# RevisionA.net
KiCad netlist of a schematic drawn in EAGLE
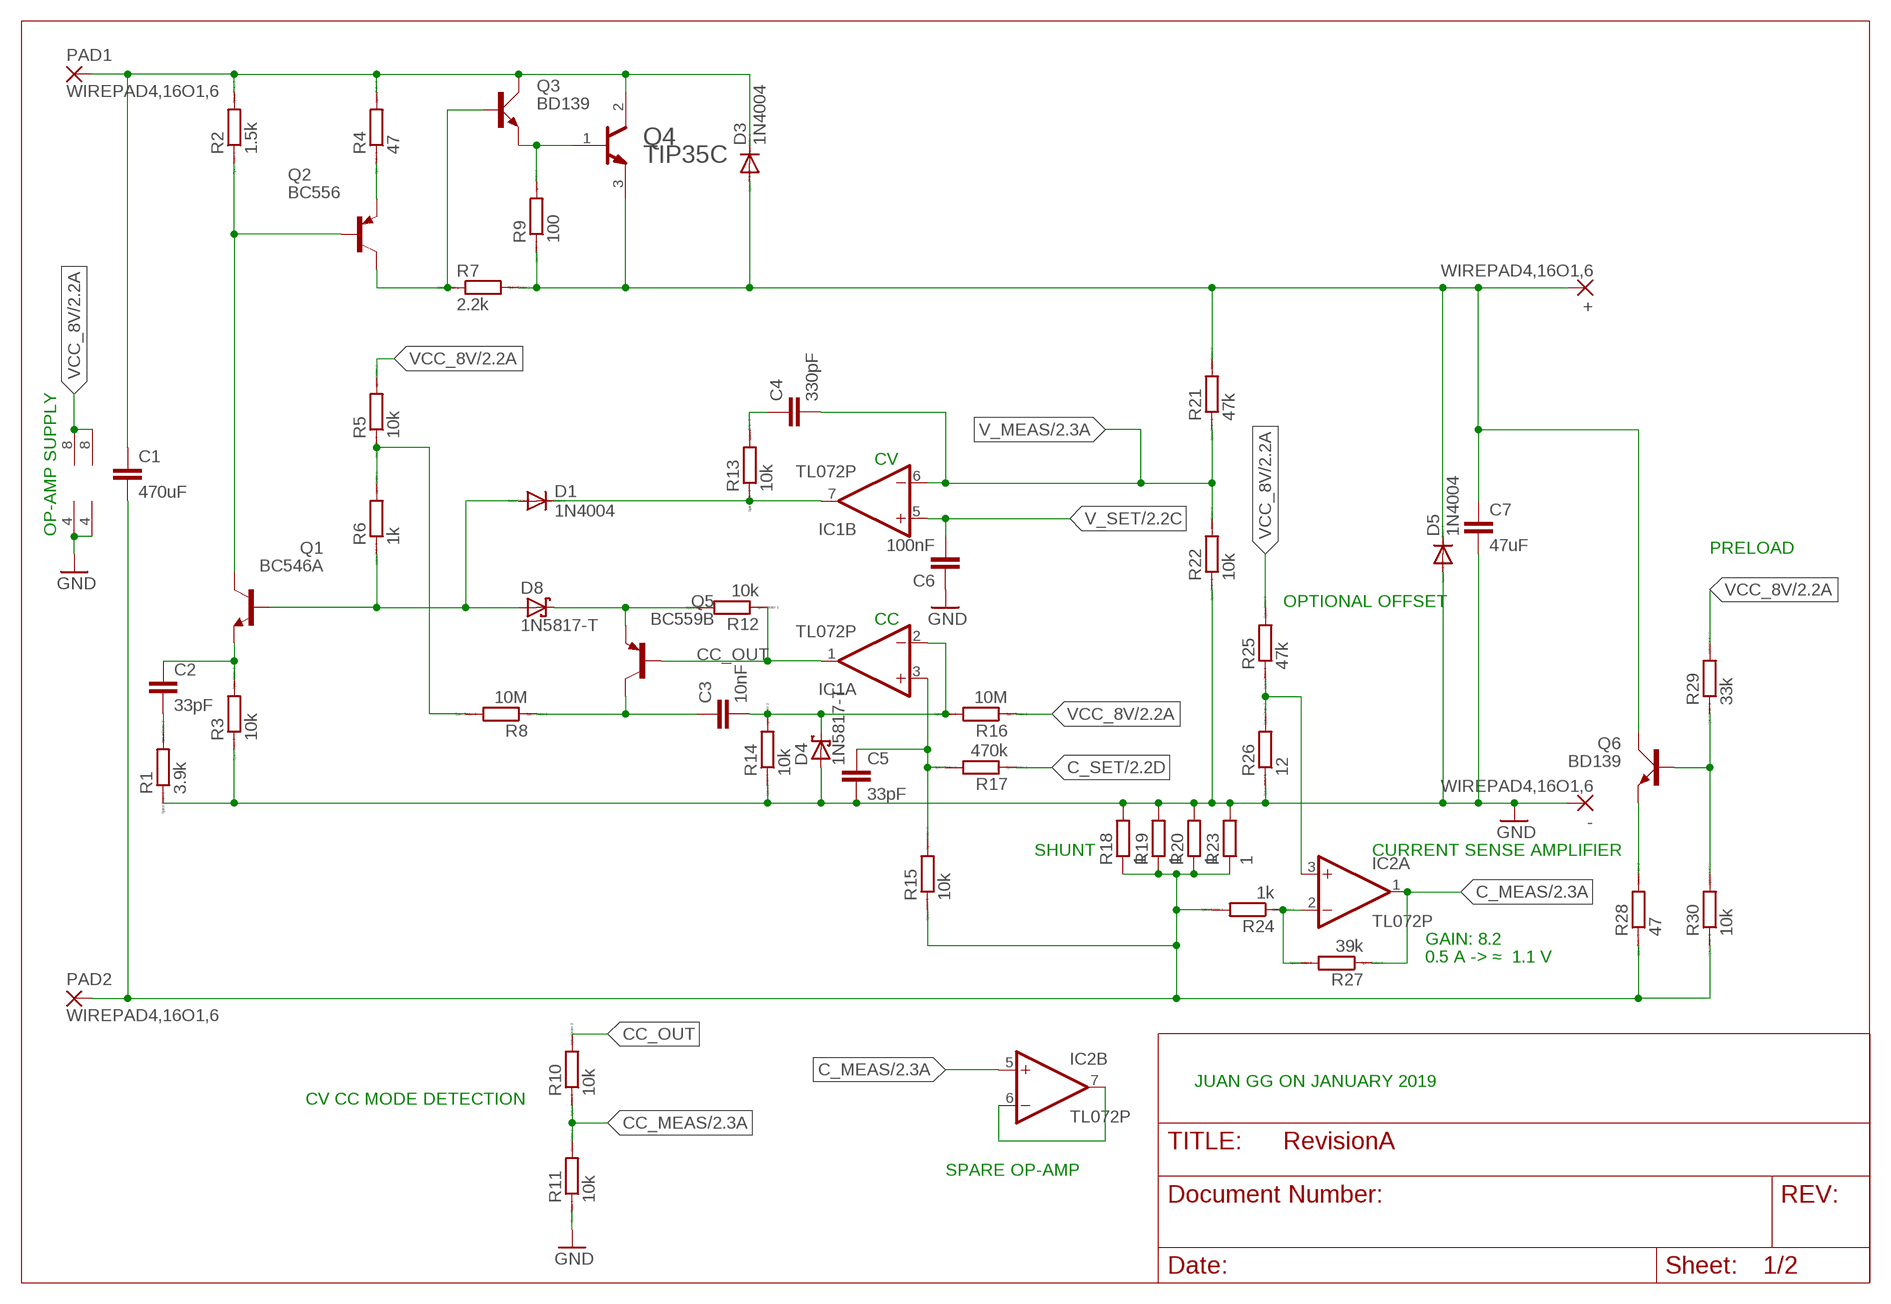
[diagram p0: schematic, sheet 1]
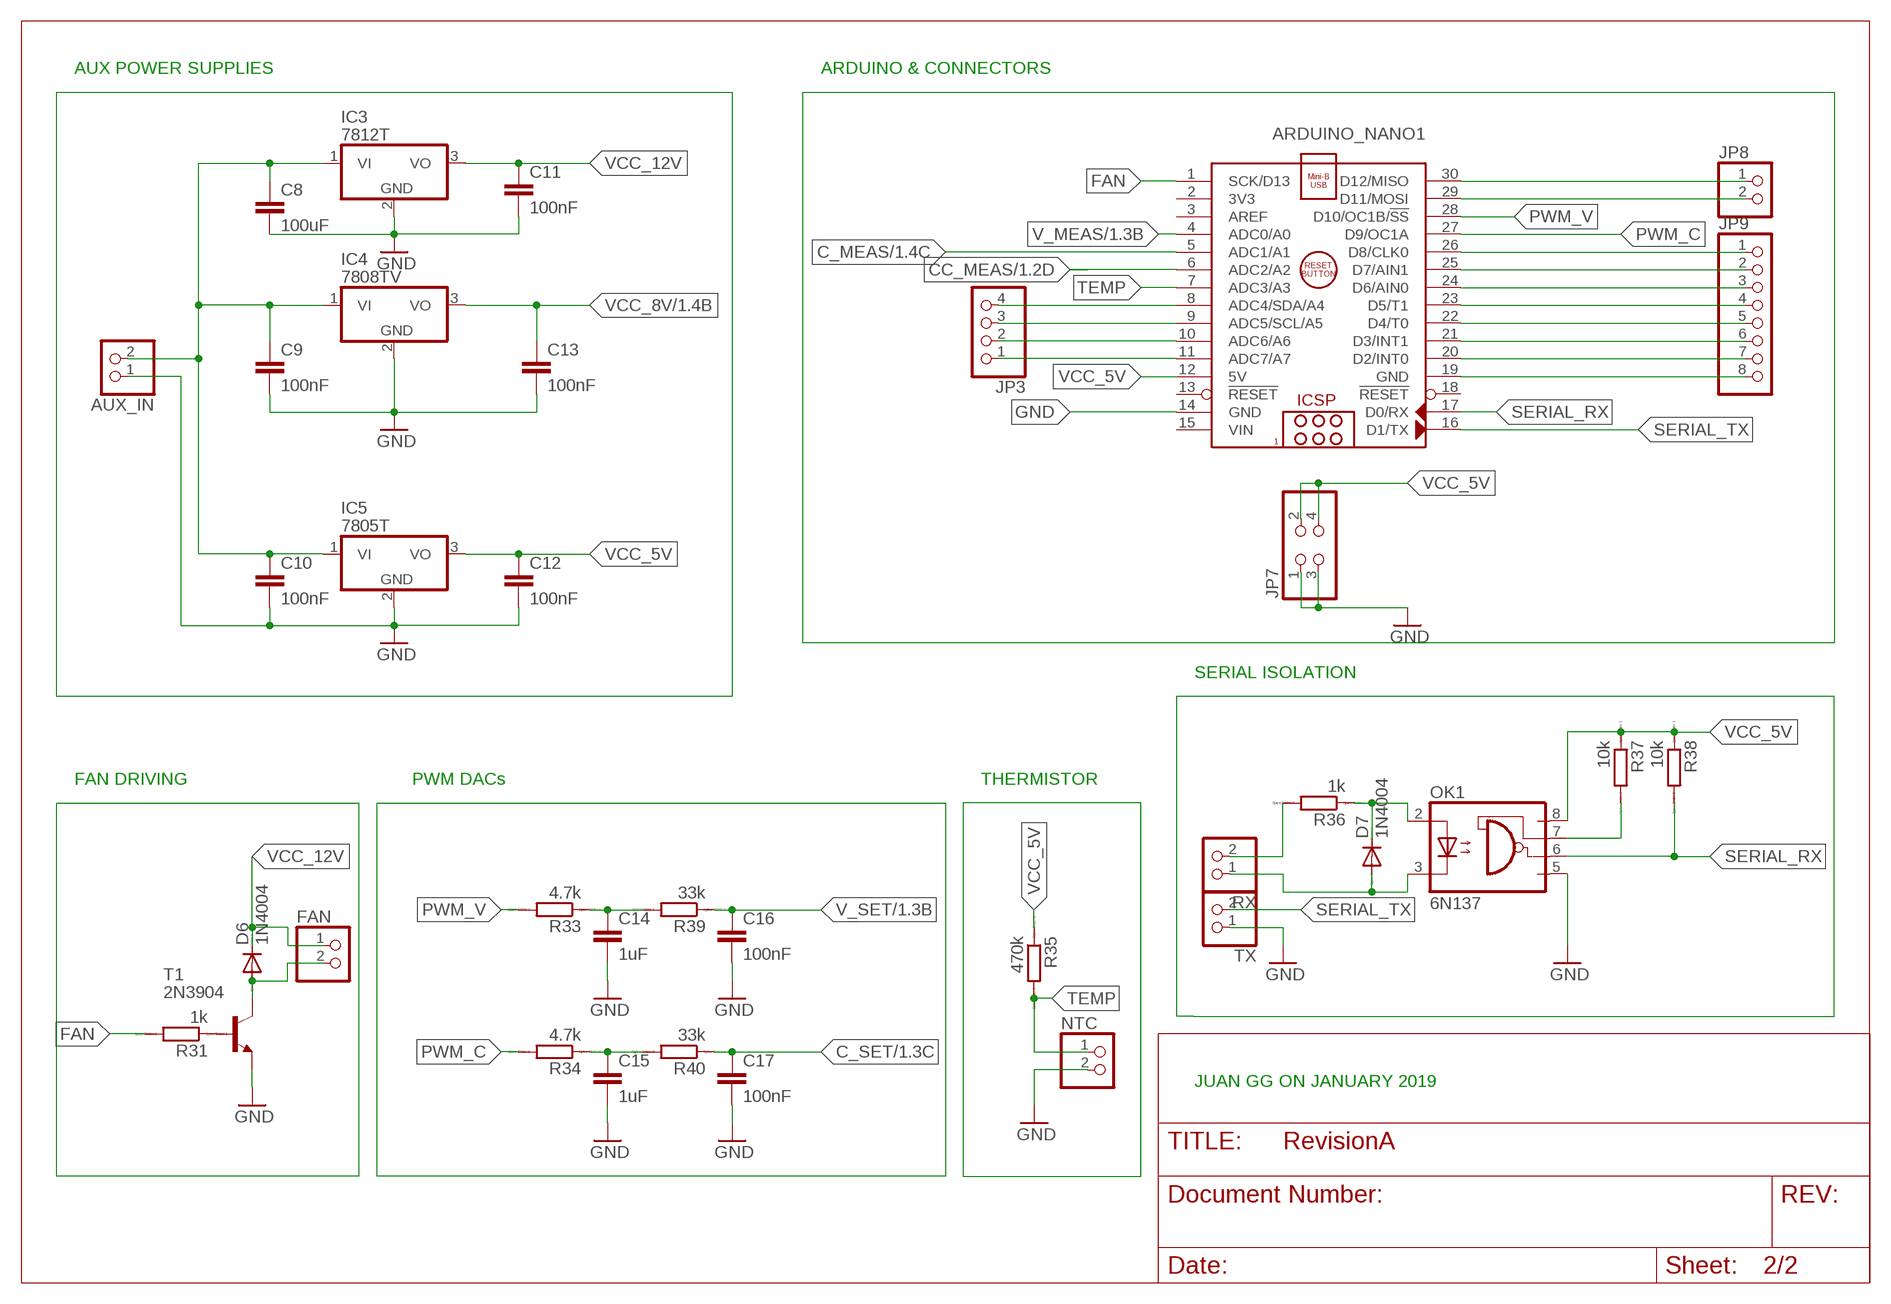
[diagram p1: schematic, sheet 2]

(export (version "E")
  (design (tool "Eeschema 10.0.6"))
  (components
    (comp (ref "+")
      (value "WIREPAD4,16O1,6")
      (footprint "eagle-import:4,16O1,6")
      (libsource (lib "eagle-import") (part "WIREPAD4,16O1,6"))
    )
    (comp (ref "-")
      (value "WIREPAD4,16O1,6")
      (footprint "eagle-import:4,16O1,6")
      (libsource (lib "eagle-import") (part "WIREPAD4,16O1,6"))
    )
    (comp (ref "C1")
      (value "470uF")
      (footprint "eagle-import:C5B7.2")
      (libsource (lib "eagle-import") (part "C5/7.2"))
    )
    (comp (ref "C2")
      (value "33pF")
      (footprint "eagle-import:C2.5-2")
      (libsource (lib "eagle-import") (part "C2.5/2"))
    )
    (comp (ref "C3")
      (value "10nF")
      (footprint "eagle-import:C2.5-2")
      (libsource (lib "eagle-import") (part "C2.5/2"))
    )
    (comp (ref "C4")
      (value "330pF")
      (footprint "eagle-import:C2.5-2")
      (libsource (lib "eagle-import") (part "C2.5/2"))
    )
    (comp (ref "C5")
      (value "33pF")
      (footprint "eagle-import:C2.5-2")
      (libsource (lib "eagle-import") (part "C2.5/2"))
    )
    (comp (ref "C6")
      (value "100nF")
      (footprint "eagle-import:C2.5-2")
      (libsource (lib "eagle-import") (part "C2.5/2"))
    )
    (comp (ref "C7")
      (value "47uF")
      (footprint "eagle-import:C5B7.2")
      (libsource (lib "eagle-import") (part "C5/7.2"))
    )
    (comp (ref "D1")
      (value "1N4004")
      (footprint "eagle-import:DO41-10")
      (libsource (lib "eagle-import") (part "1N4004"))
    )
    (comp (ref "D3")
      (value "1N4004")
      (footprint "eagle-import:DO41-10")
      (libsource (lib "eagle-import") (part "1N4004"))
    )
    (comp (ref "D4")
      (value "1N5817-T")
      (footprint "eagle-import:DO41-7.6")
      (libsource (lib "eagle-import") (part "1N5817-T"))
    )
    (comp (ref "D5")
      (value "1N4004")
      (footprint "eagle-import:DO41-10")
      (libsource (lib "eagle-import") (part "1N4004"))
    )
    (comp (ref "D8")
      (value "1N5817-T")
      (footprint "eagle-import:DO41-7.6")
      (libsource (lib "eagle-import") (part "1N5817-T"))
    )
    (comp (ref "IC1")
      (value "TL072P")
      (footprint "eagle-import:DIL08")
      (libsource (lib "eagle-import") (part "TL072P"))
    )
    (comp (ref "IC2")
      (value "TL072P")
      (footprint "eagle-import:DIL08")
      (libsource (lib "eagle-import") (part "TL072P"))
    )
    (comp (ref "PAD1")
      (value "WIREPAD4,16O1,6")
      (footprint "eagle-import:4,16O1,6")
      (libsource (lib "eagle-import") (part "WIREPAD4,16O1,6"))
    )
    (comp (ref "PAD2")
      (value "WIREPAD4,16O1,6")
      (footprint "eagle-import:4,16O1,6")
      (libsource (lib "eagle-import") (part "WIREPAD4,16O1,6"))
    )
    (comp (ref "Q1")
      (value "BC546A")
      (footprint "eagle-import:TO92-EBC")
      (libsource (lib "eagle-import") (part "BC546A"))
    )
    (comp (ref "Q2")
      (value "BC556")
      (footprint "eagle-import:TO92-EBC")
      (libsource (lib "eagle-import") (part "BC556"))
    )
    (comp (ref "Q3")
      (value "BD139")
      (footprint "eagle-import:TO126AV")
      (libsource (lib "eagle-import") (part "BD139"))
    )
    (comp (ref "Q4")
      (value "STMICROELECTRONICS_TIP35CSTMICROELECTRONICS_TIP35C_0_0")
      (footprint "eagle-import:STMICROELECTRONICS_TIP35C_0")
      (fields
        (field (name "DIGIKEY_PART_NUMBER") "497-2609-5-ND")
        (field (name "MF") "STMicroelectronics")
        (field (name "MOUSER_PART_NUMBER") "511-TIP35C")
      )
      (libsource (lib "eagle-import") (part "STMICROELECTRONICS_TIP35CSTMICROELECTRONICS_TIP35C_0_0"))
    )
    (comp (ref "Q5")
      (value "BC559B")
      (footprint "eagle-import:TO92-EBC")
      (libsource (lib "eagle-import") (part "BC559B"))
    )
    (comp (ref "Q6")
      (value "BD139")
      (footprint "eagle-import:TO126AV")
      (libsource (lib "eagle-import") (part "BD139"))
    )
    (comp (ref "R1")
      (value "3.9k")
      (footprint "eagle-import:0207_10")
      (libsource (lib "eagle-import") (part "R0207/10"))
    )
    (comp (ref "R2")
      (value "1.5k")
      (footprint "eagle-import:0207_10")
      (libsource (lib "eagle-import") (part "R0207/10"))
    )
    (comp (ref "R3")
      (value "10k")
      (footprint "eagle-import:0207_10")
      (libsource (lib "eagle-import") (part "R0207/10"))
    )
    (comp (ref "R4")
      (value "47")
      (footprint "eagle-import:0207_10")
      (libsource (lib "eagle-import") (part "R0207/10"))
    )
    (comp (ref "R5")
      (value "10k")
      (footprint "eagle-import:0207_10")
      (libsource (lib "eagle-import") (part "R0207/10"))
    )
    (comp (ref "R6")
      (value "1k")
      (footprint "eagle-import:0207_10")
      (libsource (lib "eagle-import") (part "R0207/10"))
    )
    (comp (ref "R7")
      (value "2.2k")
      (footprint "eagle-import:0207_10")
      (libsource (lib "eagle-import") (part "R0207/10"))
    )
    (comp (ref "R8")
      (value "10M")
      (footprint "eagle-import:0207_10")
      (libsource (lib "eagle-import") (part "R0207/10"))
    )
    (comp (ref "R9")
      (value "100")
      (footprint "eagle-import:0207_10")
      (libsource (lib "eagle-import") (part "R0207/10"))
    )
    (comp (ref "R10")
      (value "10k")
      (footprint "eagle-import:0207_10")
      (libsource (lib "eagle-import") (part "R0207/10"))
    )
    (comp (ref "R11")
      (value "10k")
      (footprint "eagle-import:0207_10")
      (libsource (lib "eagle-import") (part "R0207/10"))
    )
    (comp (ref "R12")
      (value "10k")
      (footprint "eagle-import:0207_10")
      (libsource (lib "eagle-import") (part "R0207/10"))
    )
    (comp (ref "R13")
      (value "10k")
      (footprint "eagle-import:0207_10")
      (libsource (lib "eagle-import") (part "R0207/10"))
    )
    (comp (ref "R14")
      (value "10k")
      (footprint "eagle-import:0207_10")
      (libsource (lib "eagle-import") (part "R0207/10"))
    )
    (comp (ref "R15")
      (value "10k")
      (footprint "eagle-import:0207_10")
      (libsource (lib "eagle-import") (part "R0207/10"))
    )
    (comp (ref "R16")
      (value "10M")
      (footprint "eagle-import:0207_10")
      (libsource (lib "eagle-import") (part "R0207/10"))
    )
    (comp (ref "R17")
      (value "470k")
      (footprint "eagle-import:0207_10")
      (libsource (lib "eagle-import") (part "R0207/10"))
    )
    (comp (ref "R18")
      (value "1")
      (footprint "eagle-import:0617V")
      (libsource (lib "eagle-import") (part "R-EU_0617/5V"))
    )
    (comp (ref "R19")
      (value "1")
      (footprint "eagle-import:0617V")
      (libsource (lib "eagle-import") (part "R-EU_0617/5V"))
    )
    (comp (ref "R20")
      (value "1")
      (footprint "eagle-import:0617V")
      (libsource (lib "eagle-import") (part "R-EU_0617/5V"))
    )
    (comp (ref "R21")
      (value "47k")
      (footprint "eagle-import:0207_10")
      (libsource (lib "eagle-import") (part "R0207/10"))
    )
    (comp (ref "R22")
      (value "10k")
      (footprint "eagle-import:0207_10")
      (libsource (lib "eagle-import") (part "R0207/10"))
    )
    (comp (ref "R23")
      (value "1")
      (footprint "eagle-import:0617V")
      (libsource (lib "eagle-import") (part "R-EU_0617/5V"))
    )
    (comp (ref "R24")
      (value "1k")
      (footprint "eagle-import:0207_10")
      (libsource (lib "eagle-import") (part "R0207/10"))
    )
    (comp (ref "R25")
      (value "47k")
      (footprint "eagle-import:0207_10")
      (libsource (lib "eagle-import") (part "R0207/10"))
    )
    (comp (ref "R26")
      (value "12")
      (footprint "eagle-import:0207_10")
      (libsource (lib "eagle-import") (part "R0207/10"))
    )
    (comp (ref "R27")
      (value "39k")
      (footprint "eagle-import:0207_10")
      (libsource (lib "eagle-import") (part "R0207/10"))
    )
    (comp (ref "R28")
      (value "47")
      (footprint "eagle-import:0207_10")
      (libsource (lib "eagle-import") (part "R0207/10"))
    )
    (comp (ref "R29")
      (value "33k")
      (footprint "eagle-import:0207_10")
      (libsource (lib "eagle-import") (part "R0207/10"))
    )
    (comp (ref "R30")
      (value "10k")
      (footprint "eagle-import:0207_10")
      (libsource (lib "eagle-import") (part "R0207/10"))
    )
    (comp (ref "ARDUINO_NANO1")
      (value "ARDUINO_NANO")
      (footprint "eagle-import:ARDUINO_NANO")
      (libsource (lib "eagle-import") (part "ARDUINO_NANO"))
    )
    (comp (ref "AUX_IN")
      (value "PINHD-1X2")
      (footprint "eagle-import:1X02")
      (libsource (lib "eagle-import") (part "PINHD-1X2"))
    )
    (comp (ref "C8")
      (value "100uF")
      (footprint "eagle-import:C2.5-4")
      (libsource (lib "eagle-import") (part "C2.5/4"))
    )
    (comp (ref "C9")
      (value "100nF")
      (footprint "eagle-import:C2.5-2")
      (libsource (lib "eagle-import") (part "C2.5/2"))
    )
    (comp (ref "C10")
      (value "100nF")
      (footprint "eagle-import:C2.5-2")
      (libsource (lib "eagle-import") (part "C2.5/2"))
    )
    (comp (ref "C11")
      (value "100nF")
      (footprint "eagle-import:C2.5-2")
      (libsource (lib "eagle-import") (part "C2.5/2"))
    )
    (comp (ref "C12")
      (value "100nF")
      (footprint "eagle-import:C2.5-2")
      (libsource (lib "eagle-import") (part "C2.5/2"))
    )
    (comp (ref "C13")
      (value "100nF")
      (footprint "eagle-import:C2.5-2")
      (libsource (lib "eagle-import") (part "C2.5/2"))
    )
    (comp (ref "C14")
      (value "1uF")
      (footprint "eagle-import:C2.5-4")
      (libsource (lib "eagle-import") (part "C2.5/4"))
    )
    (comp (ref "C15")
      (value "1uF")
      (footprint "eagle-import:C2.5-4")
      (libsource (lib "eagle-import") (part "C2.5/4"))
    )
    (comp (ref "C16")
      (value "100nF")
      (footprint "eagle-import:C2.5-4")
      (libsource (lib "eagle-import") (part "C2.5/4"))
    )
    (comp (ref "C17")
      (value "100nF")
      (footprint "eagle-import:C2.5-4")
      (libsource (lib "eagle-import") (part "C2.5/4"))
    )
    (comp (ref "D6")
      (value "1N4004")
      (footprint "eagle-import:DO41-10")
      (libsource (lib "eagle-import") (part "1N4004"))
    )
    (comp (ref "D7")
      (value "1N4004")
      (footprint "eagle-import:DO41-10")
      (libsource (lib "eagle-import") (part "1N4004"))
    )
    (comp (ref "FAN")
      (value "PINHD-1X2")
      (footprint "eagle-import:1X02")
      (libsource (lib "eagle-import") (part "PINHD-1X2"))
    )
    (comp (ref "IC3")
      (value "7812T")
      (footprint "eagle-import:TO220H")
      (libsource (lib "eagle-import") (part "78T12"))
    )
    (comp (ref "IC4")
      (value "7808TV")
      (footprint "eagle-import:TO220H")
      (libsource (lib "eagle-import") (part "78T12"))
    )
    (comp (ref "IC5")
      (value "7805T")
      (footprint "eagle-import:TO220H")
      (libsource (lib "eagle-import") (part "78T05"))
    )
    (comp (ref "JP3")
      (value "PINHD-1X4")
      (footprint "eagle-import:1X04")
      (libsource (lib "eagle-import") (part "PINHD-1X4"))
    )
    (comp (ref "JP7")
      (value "PINHD-2X2")
      (footprint "eagle-import:2X02")
      (libsource (lib "eagle-import") (part "PINHD-2X2"))
    )
    (comp (ref "JP8")
      (value "PINHD-1X2")
      (footprint "eagle-import:1X02")
      (libsource (lib "eagle-import") (part "PINHD-1X2"))
    )
    (comp (ref "JP9")
      (value "PINHD-1X8")
      (footprint "eagle-import:1X08")
      (libsource (lib "eagle-import") (part "PINHD-1X8"))
    )
    (comp (ref "NTC")
      (value "PINHD-1X2")
      (footprint "eagle-import:1X02")
      (libsource (lib "eagle-import") (part "PINHD-1X2"))
    )
    (comp (ref "OK1")
      (value "6N137")
      (footprint "eagle-import:DIL08")
      (libsource (lib "eagle-import") (part "6N137"))
    )
    (comp (ref "R31")
      (value "1k")
      (footprint "eagle-import:0207_10")
      (libsource (lib "eagle-import") (part "R0207/10"))
    )
    (comp (ref "R33")
      (value "4.7k")
      (footprint "eagle-import:0207_10")
      (libsource (lib "eagle-import") (part "R0207/10"))
    )
    (comp (ref "R34")
      (value "4.7k")
      (footprint "eagle-import:0207_10")
      (libsource (lib "eagle-import") (part "R0207/10"))
    )
    (comp (ref "R35")
      (value "470k")
      (footprint "eagle-import:0207_10")
      (libsource (lib "eagle-import") (part "R0207/10"))
    )
    (comp (ref "R36")
      (value "1k")
      (footprint "eagle-import:0207_10")
      (libsource (lib "eagle-import") (part "R0207/10"))
    )
    (comp (ref "R37")
      (value "10k")
      (footprint "eagle-import:0207_10")
      (libsource (lib "eagle-import") (part "R0207/10"))
    )
    (comp (ref "R38")
      (value "10k")
      (footprint "eagle-import:0207_10")
      (libsource (lib "eagle-import") (part "R0207/10"))
    )
    (comp (ref "R39")
      (value "33k")
      (footprint "eagle-import:0207_10")
      (libsource (lib "eagle-import") (part "R0207/10"))
    )
    (comp (ref "R40")
      (value "33k")
      (footprint "eagle-import:0207_10")
      (libsource (lib "eagle-import") (part "R0207/10"))
    )
    (comp (ref "RX")
      (value "PINHD-1X2")
      (footprint "eagle-import:1X02")
      (libsource (lib "eagle-import") (part "PINHD-1X2"))
    )
    (comp (ref "T1")
      (value "2N3904")
      (footprint "eagle-import:TO92")
      (libsource (lib "eagle-import") (part "2N3904"))
    )
    (comp (ref "TX")
      (value "PINHD-1X2")
      (footprint "eagle-import:1X02")
      (libsource (lib "eagle-import") (part "PINHD-1X2"))
    )
  )
  (nets
    (net (code "1") (name "CC_MEAS") (class "Default")
      (node (ref "ARDUINO_NANO1") (pin "6") (pinfunction "ADC2/A2_6") (pintype "bidirectional"))
      (node (ref "R10") (pin "1") (pinfunction "1_1") (pintype "passive"))
      (node (ref "R11") (pin "2") (pinfunction "2_2") (pintype "passive"))
    )
    (net (code "2") (name "CC_OUT") (class "Default")
      (node (ref "IC1") (pin "1") (pinfunction "OUT_1") (pintype "output"))
      (node (ref "Q5") (pin "B") (pinfunction "B_B") (pintype "passive"))
      (node (ref "R10") (pin "2") (pinfunction "2_2") (pintype "passive"))
      (node (ref "R12") (pin "1") (pinfunction "1_1") (pintype "passive"))
    )
    (net (code "3") (name "C_MEAS") (class "Default")
      (node (ref "ARDUINO_NANO1") (pin "5") (pinfunction "ADC1/A1_5") (pintype "bidirectional"))
      (node (ref "IC2") (pin "1") (pinfunction "OUT_1") (pintype "output"))
      (node (ref "IC2") (pin "5") (pinfunction "+IN_5") (pintype "input"))
      (node (ref "R27") (pin "1") (pinfunction "1_1") (pintype "passive"))
    )
    (net (code "4") (name "C_SET") (class "Default")
      (node (ref "C17") (pin "1") (pinfunction "1_1") (pintype "passive"))
      (node (ref "R17") (pin "1") (pinfunction "1_1") (pintype "passive"))
      (node (ref "R40") (pin "1") (pinfunction "1_1") (pintype "passive"))
    )
    (net (code "5") (name "FAN") (class "Default")
      (node (ref "ARDUINO_NANO1") (pin "1") (pinfunction "SCK/D13_1") (pintype "bidirectional"))
      (node (ref "R31") (pin "2") (pinfunction "2_2") (pintype "passive"))
    )
    (net (code "6") (name "GND") (class "Default")
      (node (ref "-") (pin "1") (pinfunction "P_1") (pintype "passive"))
      (node (ref "ARDUINO_NANO1") (pin "14") (pinfunction "GND_14") (pintype "power_in"))
      (node (ref "ARDUINO_NANO1") (pin "19") (pinfunction "GND_19") (pintype "power_in"))
      (node (ref "AUX_IN") (pin "1") (pinfunction "1_1") (pintype "passive"))
      (node (ref "C10") (pin "2") (pinfunction "2_2") (pintype "passive"))
      (node (ref "C11") (pin "2") (pinfunction "2_2") (pintype "passive"))
      (node (ref "C12") (pin "2") (pinfunction "2_2") (pintype "passive"))
      (node (ref "C13") (pin "2") (pinfunction "2_2") (pintype "passive"))
      (node (ref "C14") (pin "2") (pinfunction "2_2") (pintype "passive"))
      (node (ref "C15") (pin "2") (pinfunction "2_2") (pintype "passive"))
      (node (ref "C16") (pin "2") (pinfunction "2_2") (pintype "passive"))
      (node (ref "C17") (pin "2") (pinfunction "2_2") (pintype "passive"))
      (node (ref "C5") (pin "2") (pinfunction "2_2") (pintype "passive"))
      (node (ref "C6") (pin "1") (pinfunction "1_1") (pintype "passive"))
      (node (ref "C7") (pin "2") (pinfunction "2_2") (pintype "passive"))
      (node (ref "C8") (pin "2") (pinfunction "2_2") (pintype "passive"))
      (node (ref "C9") (pin "2") (pinfunction "2_2") (pintype "passive"))
      (node (ref "D4") (pin "A") (pinfunction "A_A") (pintype "passive"))
      (node (ref "D5") (pin "A") (pinfunction "A_A") (pintype "passive"))
      (node (ref "IC1") (pin "4") (pinfunction "V-_4") (pintype "power_in"))
      (node (ref "IC2") (pin "4") (pinfunction "V-_4") (pintype "power_in"))
      (node (ref "IC3") (pin "2") (pinfunction "GND_2") (pintype "passive"))
      (node (ref "IC4") (pin "2") (pinfunction "GND_2") (pintype "passive"))
      (node (ref "IC5") (pin "2") (pinfunction "GND_2") (pintype "passive"))
      (node (ref "JP7") (pin "1") (pinfunction "1_1") (pintype "passive"))
      (node (ref "JP7") (pin "3") (pinfunction "3_3") (pintype "passive"))
      (node (ref "JP9") (pin "8") (pinfunction "8_8") (pintype "passive"))
      (node (ref "NTC") (pin "2") (pinfunction "2_2") (pintype "passive"))
      (node (ref "OK1") (pin "5") (pinfunction "GND_5") (pintype "passive"))
      (node (ref "R1") (pin "1") (pinfunction "1_1") (pintype "passive"))
      (node (ref "R11") (pin "1") (pinfunction "1_1") (pintype "passive"))
      (node (ref "R14") (pin "1") (pinfunction "1_1") (pintype "passive"))
      (node (ref "R18") (pin "2") (pinfunction "2_2") (pintype "passive"))
      (node (ref "R19") (pin "2") (pinfunction "2_2") (pintype "passive"))
      (node (ref "R20") (pin "2") (pinfunction "2_2") (pintype "passive"))
      (node (ref "R22") (pin "1") (pinfunction "1_1") (pintype "passive"))
      (node (ref "R23") (pin "2") (pinfunction "2_2") (pintype "passive"))
      (node (ref "R26") (pin "1") (pinfunction "1_1") (pintype "passive"))
      (node (ref "R3") (pin "1") (pinfunction "1_1") (pintype "passive"))
      (node (ref "T1") (pin "3") (pinfunction "E_3") (pintype "passive"))
      (node (ref "TX") (pin "1") (pinfunction "1_1") (pintype "passive"))
    )
    (net (code "7") (name "Net-(+-P)") (class "Default")
      (node (ref "+") (pin "1") (pinfunction "P_1") (pintype "passive"))
      (node (ref "C7") (pin "1") (pinfunction "1_1") (pintype "passive"))
      (node (ref "D3") (pin "A") (pinfunction "A_A") (pintype "passive"))
      (node (ref "D5") (pin "C") (pinfunction "C_C") (pintype "passive"))
      (node (ref "Q4") (pin "3") (pinfunction "EMITTER_3") (pintype "bidirectional"))
      (node (ref "Q6") (pin "C") (pinfunction "C_C") (pintype "passive"))
      (node (ref "R21") (pin "2") (pinfunction "2_2") (pintype "passive"))
      (node (ref "R7") (pin "2") (pinfunction "2_2") (pintype "passive"))
      (node (ref "R9") (pin "1") (pinfunction "1_1") (pintype "passive"))
    )
    (net (code "8") (name "Net-(ARDUINO_NANO1-ADC4{slash}SDA{slash}A4)") (class "Default")
      (node (ref "ARDUINO_NANO1") (pin "8") (pinfunction "ADC4/SDA/A4_8") (pintype "bidirectional"))
      (node (ref "JP3") (pin "4") (pinfunction "4_4") (pintype "passive"))
    )
    (net (code "9") (name "Net-(ARDUINO_NANO1-ADC5{slash}SCL{slash}A5)") (class "Default")
      (node (ref "ARDUINO_NANO1") (pin "9") (pinfunction "ADC5/SCL/A5_9") (pintype "bidirectional"))
      (node (ref "JP3") (pin "3") (pinfunction "3_3") (pintype "passive"))
    )
    (net (code "10") (name "Net-(ARDUINO_NANO1-ADC6{slash}A6)") (class "Default")
      (node (ref "ARDUINO_NANO1") (pin "10") (pinfunction "ADC6/A6_10") (pintype "bidirectional"))
      (node (ref "JP3") (pin "2") (pinfunction "2_2") (pintype "passive"))
    )
    (net (code "11") (name "Net-(ARDUINO_NANO1-ADC7{slash}A7)") (class "Default")
      (node (ref "ARDUINO_NANO1") (pin "11") (pinfunction "ADC7/A7_11") (pintype "bidirectional"))
      (node (ref "JP3") (pin "1") (pinfunction "1_1") (pintype "passive"))
    )
    (net (code "12") (name "Net-(ARDUINO_NANO1-D2{slash}INT0)") (class "Default")
      (node (ref "ARDUINO_NANO1") (pin "20") (pinfunction "D2/INT0_20") (pintype "bidirectional"))
      (node (ref "JP9") (pin "7") (pinfunction "7_7") (pintype "passive"))
    )
    (net (code "13") (name "Net-(ARDUINO_NANO1-D3{slash}INT1)") (class "Default")
      (node (ref "ARDUINO_NANO1") (pin "21") (pinfunction "D3/INT1_21") (pintype "bidirectional"))
      (node (ref "JP9") (pin "6") (pinfunction "6_6") (pintype "passive"))
    )
    (net (code "14") (name "Net-(ARDUINO_NANO1-D4{slash}T0)") (class "Default")
      (node (ref "ARDUINO_NANO1") (pin "22") (pinfunction "D4/T0_22") (pintype "bidirectional"))
      (node (ref "JP9") (pin "5") (pinfunction "5_5") (pintype "passive"))
    )
    (net (code "15") (name "Net-(ARDUINO_NANO1-D5{slash}T1)") (class "Default")
      (node (ref "ARDUINO_NANO1") (pin "23") (pinfunction "D5/T1_23") (pintype "bidirectional"))
      (node (ref "JP9") (pin "4") (pinfunction "4_4") (pintype "passive"))
    )
    (net (code "16") (name "Net-(ARDUINO_NANO1-D6{slash}AIN0)") (class "Default")
      (node (ref "ARDUINO_NANO1") (pin "24") (pinfunction "D6/AIN0_24") (pintype "bidirectional"))
      (node (ref "JP9") (pin "3") (pinfunction "3_3") (pintype "passive"))
    )
    (net (code "17") (name "Net-(ARDUINO_NANO1-D7{slash}AIN1)") (class "Default")
      (node (ref "ARDUINO_NANO1") (pin "25") (pinfunction "D7/AIN1_25") (pintype "bidirectional"))
      (node (ref "JP9") (pin "2") (pinfunction "2_2") (pintype "passive"))
    )
    (net (code "18") (name "Net-(ARDUINO_NANO1-D8{slash}CLK0)") (class "Default")
      (node (ref "ARDUINO_NANO1") (pin "26") (pinfunction "D8/CLK0_26") (pintype "bidirectional"))
      (node (ref "JP9") (pin "1") (pinfunction "1_1") (pintype "passive"))
    )
    (net (code "19") (name "Net-(ARDUINO_NANO1-D11{slash}MOSI)") (class "Default")
      (node (ref "ARDUINO_NANO1") (pin "29") (pinfunction "D11/MOSI_29") (pintype "bidirectional"))
      (node (ref "JP8") (pin "2") (pinfunction "2_2") (pintype "passive"))
    )
    (net (code "20") (name "Net-(ARDUINO_NANO1-D12{slash}MISO)") (class "Default")
      (node (ref "ARDUINO_NANO1") (pin "30") (pinfunction "D12/MISO_30") (pintype "bidirectional"))
      (node (ref "JP8") (pin "1") (pinfunction "1_1") (pintype "passive"))
    )
    (net (code "21") (name "Net-(C2-Pad1)") (class "Default")
      (node (ref "C2") (pin "1") (pinfunction "1_1") (pintype "passive"))
      (node (ref "Q1") (pin "E") (pinfunction "E_E") (pintype "passive"))
      (node (ref "R3") (pin "2") (pinfunction "2_2") (pintype "passive"))
    )
    (net (code "22") (name "Net-(C2-Pad2)") (class "Default")
      (node (ref "C2") (pin "2") (pinfunction "2_2") (pintype "passive"))
      (node (ref "R1") (pin "2") (pinfunction "2_2") (pintype "passive"))
    )
    (net (code "23") (name "Net-(C3-Pad1)") (class "Default")
      (node (ref "C3") (pin "1") (pinfunction "1_1") (pintype "passive"))
      (node (ref "Q5") (pin "C") (pinfunction "C_C") (pintype "passive"))
      (node (ref "R8") (pin "1") (pinfunction "1_1") (pintype "passive"))
    )
    (net (code "24") (name "Net-(C4-Pad1)") (class "Default")
      (node (ref "C4") (pin "1") (pinfunction "1_1") (pintype "passive"))
      (node (ref "R13") (pin "2") (pinfunction "2_2") (pintype "passive"))
    )
    (net (code "25") (name "Net-(C14-Pad1)") (class "Default")
      (node (ref "C14") (pin "1") (pinfunction "1_1") (pintype "passive"))
      (node (ref "R33") (pin "1") (pinfunction "1_1") (pintype "passive"))
      (node (ref "R39") (pin "2") (pinfunction "2_2") (pintype "passive"))
    )
    (net (code "26") (name "Net-(C15-Pad1)") (class "Default")
      (node (ref "C15") (pin "1") (pinfunction "1_1") (pintype "passive"))
      (node (ref "R34") (pin "1") (pinfunction "1_1") (pintype "passive"))
      (node (ref "R40") (pin "2") (pinfunction "2_2") (pintype "passive"))
    )
    (net (code "27") (name "Net-(D1-PadA)") (class "Default")
      (node (ref "D1") (pin "A") (pinfunction "A_A") (pintype "passive"))
      (node (ref "D8") (pin "A") (pinfunction "A_A") (pintype "passive"))
      (node (ref "Q1") (pin "B") (pinfunction "B_B") (pintype "passive"))
      (node (ref "R6") (pin "1") (pinfunction "1_1") (pintype "passive"))
    )
    (net (code "28") (name "Net-(D8-PadC)") (class "Default")
      (node (ref "D8") (pin "C") (pinfunction "C_C") (pintype "passive"))
      (node (ref "Q5") (pin "E") (pinfunction "E_E") (pintype "passive"))
      (node (ref "R12") (pin "2") (pinfunction "2_2") (pintype "passive"))
    )
    (net (code "29") (name "Net-(IC1A-+IN)") (class "Default")
      (node (ref "C5") (pin "1") (pinfunction "1_1") (pintype "passive"))
      (node (ref "IC1") (pin "3") (pinfunction "+IN_3") (pintype "input"))
      (node (ref "R15") (pin "2") (pinfunction "2_2") (pintype "passive"))
      (node (ref "R17") (pin "2") (pinfunction "2_2") (pintype "passive"))
    )
    (net (code "30") (name "Net-(IC1A--IN)") (class "Default")
      (node (ref "C3") (pin "2") (pinfunction "2_2") (pintype "passive"))
      (node (ref "D4") (pin "C") (pinfunction "C_C") (pintype "passive"))
      (node (ref "IC1") (pin "2") (pinfunction "-IN_2") (pintype "input"))
      (node (ref "R14") (pin "2") (pinfunction "2_2") (pintype "passive"))
      (node (ref "R16") (pin "2") (pinfunction "2_2") (pintype "passive"))
    )
    (net (code "31") (name "Net-(IC1B-OUT)") (class "Default")
      (node (ref "D1") (pin "C") (pinfunction "C_C") (pintype "passive"))
      (node (ref "IC1") (pin "7") (pinfunction "OUT_7") (pintype "output"))
      (node (ref "R13") (pin "1") (pinfunction "1_1") (pintype "passive"))
    )
    (net (code "32") (name "Net-(IC2A-+IN)") (class "Default")
      (node (ref "IC2") (pin "3") (pinfunction "+IN_3") (pintype "input"))
      (node (ref "R25") (pin "1") (pinfunction "1_1") (pintype "passive"))
      (node (ref "R26") (pin "2") (pinfunction "2_2") (pintype "passive"))
    )
    (net (code "33") (name "Net-(IC2A--IN)") (class "Default")
      (node (ref "IC2") (pin "2") (pinfunction "-IN_2") (pintype "input"))
      (node (ref "R24") (pin "1") (pinfunction "1_1") (pintype "passive"))
      (node (ref "R27") (pin "2") (pinfunction "2_2") (pintype "passive"))
    )
    (net (code "34") (name "Net-(IC2B--IN)") (class "Default")
      (node (ref "IC2") (pin "6") (pinfunction "-IN_6") (pintype "input"))
      (node (ref "IC2") (pin "7") (pinfunction "OUT_7") (pintype "output"))
    )
    (net (code "35") (name "Net-(IC3-VI)") (class "Default")
      (node (ref "AUX_IN") (pin "2") (pinfunction "2_2") (pintype "passive"))
      (node (ref "C10") (pin "1") (pinfunction "1_1") (pintype "passive"))
      (node (ref "C8") (pin "1") (pinfunction "1_1") (pintype "passive"))
      (node (ref "C9") (pin "1") (pinfunction "1_1") (pintype "passive"))
      (node (ref "IC3") (pin "1") (pinfunction "VI_1") (pintype "input"))
      (node (ref "IC4") (pin "1") (pinfunction "VI_1") (pintype "input"))
      (node (ref "IC5") (pin "1") (pinfunction "VI_1") (pintype "input"))
    )
    (net (code "36") (name "Net-(OK1-A)") (class "Default")
      (node (ref "D7") (pin "C") (pinfunction "C_C") (pintype "passive"))
      (node (ref "OK1") (pin "2") (pinfunction "A_2") (pintype "passive"))
      (node (ref "R36") (pin "1") (pinfunction "1_1") (pintype "passive"))
    )
    (net (code "37") (name "Net-(OK1-C)") (class "Default")
      (node (ref "D7") (pin "A") (pinfunction "A_A") (pintype "passive"))
      (node (ref "OK1") (pin "3") (pinfunction "C_3") (pintype "passive"))
      (node (ref "RX") (pin "1") (pinfunction "1_1") (pintype "passive"))
    )
    (net (code "38") (name "Net-(OK1-VE)") (class "Default")
      (node (ref "OK1") (pin "7") (pinfunction "VE_7") (pintype "passive"))
      (node (ref "R37") (pin "2") (pinfunction "2_2") (pintype "passive"))
    )
    (net (code "39") (name "Net-(PAD1-P)") (class "Default")
      (node (ref "C1") (pin "1") (pinfunction "1_1") (pintype "passive"))
      (node (ref "D3") (pin "C") (pinfunction "C_C") (pintype "passive"))
      (node (ref "PAD1") (pin "1") (pinfunction "P_1") (pintype "passive"))
      (node (ref "Q3") (pin "C") (pinfunction "C_C") (pintype "passive"))
      (node (ref "Q4") (pin "2") (pinfunction "COLLECTOR_2") (pintype "bidirectional"))
      (node (ref "R2") (pin "2") (pinfunction "2_2") (pintype "passive"))
      (node (ref "R4") (pin "2") (pinfunction "2_2") (pintype "passive"))
    )
    (net (code "40") (name "Net-(PAD2-P)") (class "Default")
      (node (ref "C1") (pin "2") (pinfunction "2_2") (pintype "passive"))
      (node (ref "PAD2") (pin "1") (pinfunction "P_1") (pintype "passive"))
      (node (ref "R15") (pin "1") (pinfunction "1_1") (pintype "passive"))
      (node (ref "R18") (pin "1") (pinfunction "1_1") (pintype "passive"))
      (node (ref "R19") (pin "1") (pinfunction "1_1") (pintype "passive"))
      (node (ref "R20") (pin "1") (pinfunction "1_1") (pintype "passive"))
      (node (ref "R23") (pin "1") (pinfunction "1_1") (pintype "passive"))
      (node (ref "R24") (pin "2") (pinfunction "2_2") (pintype "passive"))
      (node (ref "R28") (pin "1") (pinfunction "1_1") (pintype "passive"))
      (node (ref "R30") (pin "1") (pinfunction "1_1") (pintype "passive"))
    )
    (net (code "41") (name "Net-(Q1-PadC)") (class "Default")
      (node (ref "Q1") (pin "C") (pinfunction "C_C") (pintype "passive"))
      (node (ref "Q2") (pin "B") (pinfunction "B_B") (pintype "passive"))
      (node (ref "R2") (pin "1") (pinfunction "1_1") (pintype "passive"))
    )
    (net (code "42") (name "Net-(Q2-PadC)") (class "Default")
      (node (ref "Q2") (pin "C") (pinfunction "C_C") (pintype "passive"))
      (node (ref "Q3") (pin "B") (pinfunction "B_B") (pintype "passive"))
      (node (ref "R7") (pin "1") (pinfunction "1_1") (pintype "passive"))
    )
    (net (code "43") (name "Net-(Q2-PadE)") (class "Default")
      (node (ref "Q2") (pin "E") (pinfunction "E_E") (pintype "passive"))
      (node (ref "R4") (pin "1") (pinfunction "1_1") (pintype "passive"))
    )
    (net (code "44") (name "Net-(Q4-BASE)") (class "Default")
      (node (ref "Q3") (pin "E") (pinfunction "E_E") (pintype "passive"))
      (node (ref "Q4") (pin "1") (pinfunction "BASE_1") (pintype "bidirectional"))
      (node (ref "R9") (pin "2") (pinfunction "2_2") (pintype "passive"))
    )
    (net (code "45") (name "Net-(Q6-PadB)") (class "Default")
      (node (ref "Q6") (pin "B") (pinfunction "B_B") (pintype "passive"))
      (node (ref "R29") (pin "1") (pinfunction "1_1") (pintype "passive"))
      (node (ref "R30") (pin "2") (pinfunction "2_2") (pintype "passive"))
    )
    (net (code "46") (name "Net-(Q6-PadE)") (class "Default")
      (node (ref "Q6") (pin "E") (pinfunction "E_E") (pintype "passive"))
      (node (ref "R28") (pin "2") (pinfunction "2_2") (pintype "passive"))
    )
    (net (code "47") (name "Net-(R5-Pad1)") (class "Default")
      (node (ref "R5") (pin "1") (pinfunction "1_1") (pintype "passive"))
      (node (ref "R6") (pin "2") (pinfunction "2_2") (pintype "passive"))
      (node (ref "R8") (pin "2") (pinfunction "2_2") (pintype "passive"))
    )
    (net (code "48") (name "Net-(R36-Pad2)") (class "Default")
      (node (ref "R36") (pin "2") (pinfunction "2_2") (pintype "passive"))
      (node (ref "RX") (pin "2") (pinfunction "2_2") (pintype "passive"))
    )
    (net (code "49") (name "Net-(T1-B)") (class "Default")
      (node (ref "R31") (pin "1") (pinfunction "1_1") (pintype "passive"))
      (node (ref "T1") (pin "2") (pinfunction "B_2") (pintype "passive"))
    )
    (net (code "50") (name "Net-(T1-C)") (class "Default")
      (node (ref "D6") (pin "A") (pinfunction "A_A") (pintype "passive"))
      (node (ref "FAN") (pin "2") (pinfunction "2_2") (pintype "passive"))
      (node (ref "T1") (pin "1") (pinfunction "C_1") (pintype "passive"))
    )
    (net (code "51") (name "PWM_C") (class "Default")
      (node (ref "ARDUINO_NANO1") (pin "27") (pinfunction "D9/OC1A_27") (pintype "bidirectional"))
      (node (ref "R34") (pin "2") (pinfunction "2_2") (pintype "passive"))
    )
    (net (code "52") (name "PWM_V") (class "Default")
      (node (ref "ARDUINO_NANO1") (pin "28") (pinfunction "D10/OC1B/~{SS}_28") (pintype "bidirectional"))
      (node (ref "R33") (pin "2") (pinfunction "2_2") (pintype "passive"))
    )
    (net (code "53") (name "SERIAL_RX") (class "Default")
      (node (ref "ARDUINO_NANO1") (pin "17") (pinfunction "D0/RX_17") (pintype "bidirectional"))
      (node (ref "OK1") (pin "6") (pinfunction "VO_6") (pintype "passive"))
      (node (ref "R38") (pin "2") (pinfunction "2_2") (pintype "passive"))
    )
    (net (code "54") (name "SERIAL_TX") (class "Default")
      (node (ref "ARDUINO_NANO1") (pin "16") (pinfunction "D1/TX_16") (pintype "bidirectional"))
      (node (ref "TX") (pin "2") (pinfunction "2_2") (pintype "passive"))
    )
    (net (code "55") (name "TEMP") (class "Default")
      (node (ref "ARDUINO_NANO1") (pin "7") (pinfunction "ADC3/A3_7") (pintype "bidirectional"))
      (node (ref "NTC") (pin "1") (pinfunction "1_1") (pintype "passive"))
      (node (ref "R35") (pin "2") (pinfunction "2_2") (pintype "passive"))
    )
    (net (code "56") (name "VCC_5V") (class "Default")
      (node (ref "ARDUINO_NANO1") (pin "12") (pinfunction "5V_12") (pintype "power_in"))
      (node (ref "C12") (pin "1") (pinfunction "1_1") (pintype "passive"))
      (node (ref "IC5") (pin "3") (pinfunction "VO_3") (pintype "passive"))
      (node (ref "JP7") (pin "2") (pinfunction "2_2") (pintype "passive"))
      (node (ref "JP7") (pin "4") (pinfunction "4_4") (pintype "passive"))
      (node (ref "OK1") (pin "8") (pinfunction "VCC_8") (pintype "passive"))
      (node (ref "R35") (pin "1") (pinfunction "1_1") (pintype "passive"))
      (node (ref "R37") (pin "1") (pinfunction "1_1") (pintype "passive"))
      (node (ref "R38") (pin "1") (pinfunction "1_1") (pintype "passive"))
    )
    (net (code "57") (name "VCC_8V") (class "Default")
      (node (ref "C13") (pin "1") (pinfunction "1_1") (pintype "passive"))
      (node (ref "IC1") (pin "8") (pinfunction "V+_8") (pintype "power_in"))
      (node (ref "IC2") (pin "8") (pinfunction "V+_8") (pintype "power_in"))
      (node (ref "IC4") (pin "3") (pinfunction "VO_3") (pintype "passive"))
      (node (ref "R16") (pin "1") (pinfunction "1_1") (pintype "passive"))
      (node (ref "R25") (pin "2") (pinfunction "2_2") (pintype "passive"))
      (node (ref "R29") (pin "2") (pinfunction "2_2") (pintype "passive"))
      (node (ref "R5") (pin "2") (pinfunction "2_2") (pintype "passive"))
    )
    (net (code "58") (name "VCC_12V") (class "Default")
      (node (ref "C11") (pin "1") (pinfunction "1_1") (pintype "passive"))
      (node (ref "D6") (pin "C") (pinfunction "C_C") (pintype "passive"))
      (node (ref "FAN") (pin "1") (pinfunction "1_1") (pintype "passive"))
      (node (ref "IC3") (pin "3") (pinfunction "VO_3") (pintype "passive"))
    )
    (net (code "59") (name "VIN") (class "Default")
      (node (ref "ARDUINO_NANO1") (pin "15") (pinfunction "VIN_15") (pintype "power_in"))
    )
    (net (code "60") (name "V_MEAS") (class "Default")
      (node (ref "ARDUINO_NANO1") (pin "4") (pinfunction "ADC0/A0_4") (pintype "bidirectional"))
      (node (ref "C4") (pin "2") (pinfunction "2_2") (pintype "passive"))
      (node (ref "IC1") (pin "6") (pinfunction "-IN_6") (pintype "input"))
      (node (ref "R21") (pin "1") (pinfunction "1_1") (pintype "passive"))
      (node (ref "R22") (pin "2") (pinfunction "2_2") (pintype "passive"))
    )
    (net (code "61") (name "V_SET") (class "Default")
      (node (ref "C16") (pin "1") (pinfunction "1_1") (pintype "passive"))
      (node (ref "C6") (pin "2") (pinfunction "2_2") (pintype "passive"))
      (node (ref "IC1") (pin "5") (pinfunction "+IN_5") (pintype "input"))
      (node (ref "R39") (pin "1") (pinfunction "1_1") (pintype "passive"))
    )
    (net (code "62") (name "unconnected-(ARDUINO_NANO1-3V3-Pad2)") (class "Default")
      (node (ref "ARDUINO_NANO1") (pin "2") (pinfunction "3V3_2") (pintype "output"))
    )
    (net (code "63") (name "unconnected-(ARDUINO_NANO1-AREF-Pad3)") (class "Default")
      (node (ref "ARDUINO_NANO1") (pin "3") (pinfunction "AREF_3") (pintype "input"))
    )
    (net (code "64") (name "unconnected-(ARDUINO_NANO1-~{RESET}-Pad13)") (class "Default")
      (node (ref "ARDUINO_NANO1") (pin "13") (pinfunction "~{RESET}_13") (pintype "input"))
    )
    (net (code "65") (name "unconnected-(ARDUINO_NANO1-~{RESET}-Pad18)") (class "Default")
      (node (ref "ARDUINO_NANO1") (pin "18") (pinfunction "~{RESET}_18") (pintype "input"))
    )
  )
)
